# tuner.net
KiCad netlist of a schematic drawn in EAGLE
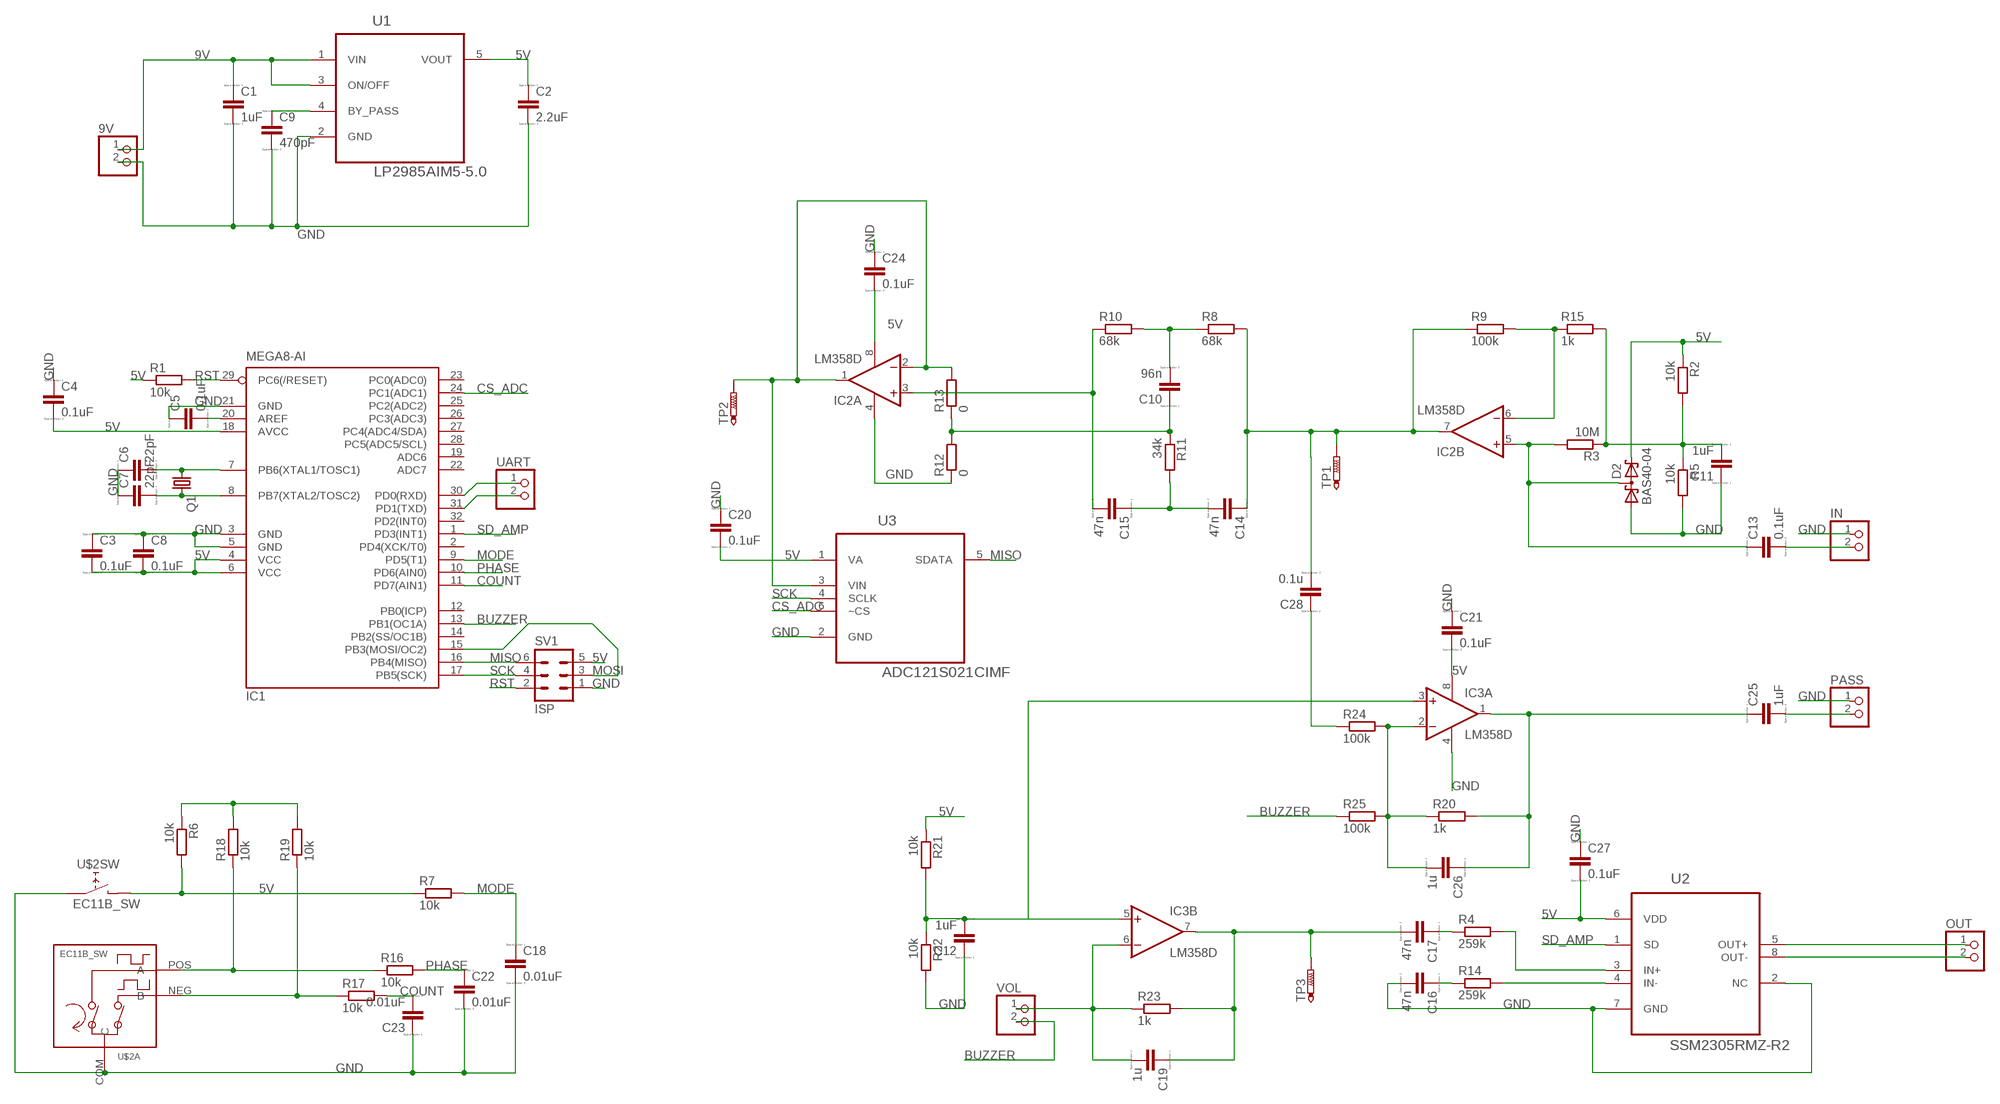
[diagram p0: schematic, sheet 1]

(export (version "E")
  (design (tool "Eeschema 10.0.6"))
  (components
    (comp (ref "9V")
      (value "PINHD-1X2")
      (footprint "eagle-import:1X02")
      (libsource (lib "eagle-import") (part "PINHD-1X2"))
    )
    (comp (ref "C1")
      (value "1uF")
      (footprint "eagle-import:C0805")
      (libsource (lib "eagle-import") (part "C"))
    )
    (comp (ref "C2")
      (value "2.2uF")
      (footprint "eagle-import:C0805")
      (libsource (lib "eagle-import") (part "C"))
    )
    (comp (ref "C3")
      (value "0.1uF")
      (footprint "eagle-import:C0805")
      (libsource (lib "eagle-import") (part "C"))
    )
    (comp (ref "C4")
      (value "0.1uF")
      (footprint "eagle-import:C0805")
      (libsource (lib "eagle-import") (part "C"))
    )
    (comp (ref "C5")
      (value "0.1uF")
      (footprint "eagle-import:C0805")
      (libsource (lib "eagle-import") (part "C"))
    )
    (comp (ref "C6")
      (value "22pF")
      (footprint "eagle-import:C0805")
      (libsource (lib "eagle-import") (part "C"))
    )
    (comp (ref "C7")
      (value "22pF")
      (footprint "eagle-import:C0805")
      (libsource (lib "eagle-import") (part "C"))
    )
    (comp (ref "C8")
      (value "0.1uF")
      (footprint "eagle-import:C0805")
      (libsource (lib "eagle-import") (part "C"))
    )
    (comp (ref "C9")
      (value "470pF")
      (footprint "eagle-import:C0805")
      (libsource (lib "eagle-import") (part "C"))
    )
    (comp (ref "C10")
      (value "96n")
      (footprint "eagle-import:C0805")
      (libsource (lib "eagle-import") (part "C"))
    )
    (comp (ref "C11")
      (value "1uF")
      (footprint "eagle-import:C0805")
      (libsource (lib "eagle-import") (part "C"))
    )
    (comp (ref "C12")
      (value "1uF")
      (footprint "eagle-import:C0805")
      (libsource (lib "eagle-import") (part "C"))
    )
    (comp (ref "C13")
      (value "0.1uF")
      (footprint "eagle-import:C0805")
      (libsource (lib "eagle-import") (part "C"))
    )
    (comp (ref "C14")
      (value "47n")
      (footprint "eagle-import:C0805")
      (libsource (lib "eagle-import") (part "C"))
    )
    (comp (ref "C15")
      (value "47n")
      (footprint "eagle-import:C0805")
      (libsource (lib "eagle-import") (part "C"))
    )
    (comp (ref "C16")
      (value "47n")
      (footprint "eagle-import:C0805")
      (libsource (lib "eagle-import") (part "C"))
    )
    (comp (ref "C17")
      (value "47n")
      (footprint "eagle-import:C0805")
      (libsource (lib "eagle-import") (part "C"))
    )
    (comp (ref "C18")
      (value "0.01uF")
      (footprint "eagle-import:C0805")
      (libsource (lib "eagle-import") (part "C"))
    )
    (comp (ref "C19")
      (value "1u")
      (footprint "eagle-import:C0805")
      (libsource (lib "eagle-import") (part "C"))
    )
    (comp (ref "C20")
      (value "0.1uF")
      (footprint "eagle-import:C0805")
      (libsource (lib "eagle-import") (part "C"))
    )
    (comp (ref "C21")
      (value "0.1uF")
      (footprint "eagle-import:C0805")
      (libsource (lib "eagle-import") (part "C"))
    )
    (comp (ref "C22")
      (value "0.01uF")
      (footprint "eagle-import:C0805")
      (libsource (lib "eagle-import") (part "C"))
    )
    (comp (ref "C23")
      (value "0.01uF")
      (footprint "eagle-import:C0805")
      (libsource (lib "eagle-import") (part "C"))
    )
    (comp (ref "C24")
      (value "0.1uF")
      (footprint "eagle-import:C0805")
      (libsource (lib "eagle-import") (part "C"))
    )
    (comp (ref "C25")
      (value "1uF")
      (footprint "eagle-import:C0805")
      (libsource (lib "eagle-import") (part "C"))
    )
    (comp (ref "C26")
      (value "1u")
      (footprint "eagle-import:C0805")
      (libsource (lib "eagle-import") (part "C"))
    )
    (comp (ref "C27")
      (value "0.1uF")
      (footprint "eagle-import:C0805")
      (libsource (lib "eagle-import") (part "C"))
    )
    (comp (ref "C28")
      (value "0.1u")
      (footprint "eagle-import:C0805")
      (libsource (lib "eagle-import") (part "C"))
    )
    (comp (ref "D2")
      (value "BAS40-04")
      (footprint "eagle-import:SOT23")
      (libsource (lib "eagle-import") (part "BAS40-04"))
    )
    (comp (ref "IC1")
      (value "MEGA8-AI")
      (footprint "eagle-import:TQFP32-08")
      (fields (field (name "MPN") "ATMEGA8-16AU"))
      (libsource (lib "eagle-import") (part "MEGA8-AI"))
    )
    (comp (ref "IC2")
      (value "LM358D")
      (footprint "eagle-import:SO08")
      (libsource (lib "eagle-import") (part "LM358D"))
    )
    (comp (ref "IC3")
      (value "LM358D")
      (footprint "eagle-import:SO08")
      (libsource (lib "eagle-import") (part "LM358D"))
    )
    (comp (ref "IN")
      (value "PINHD-1X2")
      (footprint "eagle-import:1X02")
      (libsource (lib "eagle-import") (part "PINHD-1X2"))
    )
    (comp (ref "OUT")
      (value "PINHD-1X2")
      (footprint "eagle-import:1X02")
      (libsource (lib "eagle-import") (part "PINHD-1X2"))
    )
    (comp (ref "PASS")
      (value "PINHD-1X2")
      (footprint "eagle-import:1X02")
      (libsource (lib "eagle-import") (part "PINHD-1X2"))
    )
    (comp (ref "Q1")
      (value "CRYSTALHC49S")
      (footprint "eagle-import:HC49_S")
      (libsource (lib "eagle-import") (part "CRYSTALHC49S"))
    )
    (comp (ref "R1")
      (value "10k")
      (footprint "eagle-import:M0805")
      (libsource (lib "eagle-import") (part "R-EU_M0805"))
    )
    (comp (ref "R2")
      (value "10k")
      (footprint "eagle-import:M0805")
      (libsource (lib "eagle-import") (part "R-EU_M0805"))
    )
    (comp (ref "R3")
      (value "10M")
      (footprint "eagle-import:M0805")
      (libsource (lib "eagle-import") (part "R-EU_M0805"))
    )
    (comp (ref "R4")
      (value "259k")
      (footprint "eagle-import:M0805")
      (libsource (lib "eagle-import") (part "R-EU_M0805"))
    )
    (comp (ref "R5")
      (value "10k")
      (footprint "eagle-import:M0805")
      (libsource (lib "eagle-import") (part "R-EU_M0805"))
    )
    (comp (ref "R6")
      (value "10k")
      (footprint "eagle-import:M0805")
      (libsource (lib "eagle-import") (part "R-EU_M0805"))
    )
    (comp (ref "R7")
      (value "10k")
      (footprint "eagle-import:M0805")
      (libsource (lib "eagle-import") (part "R-EU_M0805"))
    )
    (comp (ref "R8")
      (value "68k")
      (footprint "eagle-import:M0805")
      (libsource (lib "eagle-import") (part "R-EU_M0805"))
    )
    (comp (ref "R9")
      (value "100k")
      (footprint "eagle-import:M0805")
      (libsource (lib "eagle-import") (part "R-EU_M0805"))
    )
    (comp (ref "R10")
      (value "68k")
      (footprint "eagle-import:M0805")
      (libsource (lib "eagle-import") (part "R-EU_M0805"))
    )
    (comp (ref "R11")
      (value "34k")
      (footprint "eagle-import:M0805")
      (libsource (lib "eagle-import") (part "R-EU_M0805"))
    )
    (comp (ref "R12")
      (value "0")
      (footprint "eagle-import:M0805")
      (libsource (lib "eagle-import") (part "R-EU_M0805"))
    )
    (comp (ref "R13")
      (value "0")
      (footprint "eagle-import:M0805")
      (libsource (lib "eagle-import") (part "R-EU_M0805"))
    )
    (comp (ref "R14")
      (value "259k")
      (footprint "eagle-import:M0805")
      (libsource (lib "eagle-import") (part "R-EU_M0805"))
    )
    (comp (ref "R15")
      (value "1k")
      (footprint "eagle-import:M0805")
      (libsource (lib "eagle-import") (part "R-EU_M0805"))
    )
    (comp (ref "R16")
      (value "10k")
      (footprint "eagle-import:M0805")
      (libsource (lib "eagle-import") (part "R-EU_M0805"))
    )
    (comp (ref "R17")
      (value "10k")
      (footprint "eagle-import:M0805")
      (libsource (lib "eagle-import") (part "R-EU_M0805"))
    )
    (comp (ref "R18")
      (value "10k")
      (footprint "eagle-import:M0805")
      (libsource (lib "eagle-import") (part "R-EU_M0805"))
    )
    (comp (ref "R19")
      (value "10k")
      (footprint "eagle-import:M0805")
      (libsource (lib "eagle-import") (part "R-EU_M0805"))
    )
    (comp (ref "R20")
      (value "1k")
      (footprint "eagle-import:M0805")
      (libsource (lib "eagle-import") (part "R-EU_M0805"))
    )
    (comp (ref "R21")
      (value "10k")
      (footprint "eagle-import:M0805")
      (libsource (lib "eagle-import") (part "R-EU_M0805"))
    )
    (comp (ref "R22")
      (value "10k")
      (footprint "eagle-import:M0805")
      (libsource (lib "eagle-import") (part "R-EU_M0805"))
    )
    (comp (ref "R23")
      (value "1k")
      (footprint "eagle-import:M0805")
      (libsource (lib "eagle-import") (part "R-EU_M0805"))
    )
    (comp (ref "R24")
      (value "100k")
      (footprint "eagle-import:M0805")
      (libsource (lib "eagle-import") (part "R-EU_M0805"))
    )
    (comp (ref "R25")
      (value "100k")
      (footprint "eagle-import:M0805")
      (libsource (lib "eagle-import") (part "R-EU_M0805"))
    )
    (comp (ref "SV1")
      (value "ISP")
      (footprint "eagle-import:MA03-2")
      (libsource (lib "eagle-import") (part "MA03-2"))
    )
    (comp (ref "TP1")
      (value "PTR1B1,27")
      (footprint "eagle-import:B1,27")
      (libsource (lib "eagle-import") (part "PTR1B1,27"))
    )
    (comp (ref "TP2")
      (value "PTR1B1,27")
      (footprint "eagle-import:B1,27")
      (libsource (lib "eagle-import") (part "PTR1B1,27"))
    )
    (comp (ref "TP3")
      (value "PTR1B1,27")
      (footprint "eagle-import:B1,27")
      (libsource (lib "eagle-import") (part "PTR1B1,27"))
    )
    (comp (ref "U$2")
      (value "EC11B_SW")
      (footprint "eagle-import:EC11B")
      (libsource (lib "eagle-import") (part "EC11B_SW"))
    )
    (comp (ref "U1")
      (value "LP2985AIM5-5.0")
      (footprint "eagle-import:SOT95P284X119-5N")
      (fields (field (name "MF") "Texas Instruments") (field (name "MP") "LP2985AIM5-5.0/NOPB"))
      (libsource (lib "eagle-import") (part "LP2985AIM5-5.0"))
    )
    (comp (ref "U2")
      (value "SSM2305RMZ-R2")
      (footprint "eagle-import:SOP65P490X110-8N")
      (fields (field (name "MF") "Analog Devices"))
      (libsource (lib "eagle-import") (part "SSM2305RMZ-R2"))
    )
    (comp (ref "U3")
      (value "ADC121S021CIMF")
      (footprint "eagle-import:SOT95P284X122-6N")
      (fields (field (name "MF") "Texas Instruments") (field (name "MP") "ADC121S021CIMF/NOPB"))
      (libsource (lib "eagle-import") (part "ADC121S021CIMF"))
    )
    (comp (ref "UART")
      (value "PINHD-1X2")
      (footprint "eagle-import:1X02")
      (libsource (lib "eagle-import") (part "PINHD-1X2"))
    )
    (comp (ref "VOL")
      (value "PINHD-1X2")
      (footprint "eagle-import:1X02")
      (libsource (lib "eagle-import") (part "PINHD-1X2"))
    )
  )
  (nets
    (net (code "1") (name "/5V") (class "Default")
      (node (ref "C2") (pin "1") (pinfunction "1_1") (pintype "passive"))
      (node (ref "C20") (pin "2") (pinfunction "2_2") (pintype "passive"))
      (node (ref "C21") (pin "2") (pinfunction "2_2") (pintype "passive"))
      (node (ref "C24") (pin "2") (pinfunction "2_2") (pintype "passive"))
      (node (ref "C27") (pin "2") (pinfunction "2_2") (pintype "passive"))
      (node (ref "C3") (pin "2") (pinfunction "2_2") (pintype "passive"))
      (node (ref "C4") (pin "2") (pinfunction "2_2") (pintype "passive"))
      (node (ref "C8") (pin "2") (pinfunction "2_2") (pintype "passive"))
      (node (ref "D2") (pin "2") (pinfunction "C2_2") (pintype "passive"))
      (node (ref "IC1") (pin "18") (pinfunction "AVCC_18") (pintype "power_in"))
      (node (ref "IC1") (pin "4") (pinfunction "VCC_4") (pintype "power_in"))
      (node (ref "IC1") (pin "6") (pinfunction "VCC_6") (pintype "power_in"))
      (node (ref "IC2") (pin "8") (pinfunction "V+_8") (pintype "power_in"))
      (node (ref "IC3") (pin "8") (pinfunction "V+_8") (pintype "power_in"))
      (node (ref "R1") (pin "1") (pinfunction "1_1") (pintype "passive"))
      (node (ref "R18") (pin "2") (pinfunction "2_2") (pintype "passive"))
      (node (ref "R19") (pin "2") (pinfunction "2_2") (pintype "passive"))
      (node (ref "R2") (pin "1") (pinfunction "1_1") (pintype "passive"))
      (node (ref "R21") (pin "1") (pinfunction "1_1") (pintype "passive"))
      (node (ref "R6") (pin "1") (pinfunction "1_1") (pintype "passive"))
      (node (ref "SV1") (pin "5") (pinfunction "5_5") (pintype "passive"))
      (node (ref "U1") (pin "5") (pinfunction "VOUT_5") (pintype "output"))
      (node (ref "U2") (pin "6") (pinfunction "VDD_6") (pintype "power_in"))
      (node (ref "U3") (pin "1") (pinfunction "VA_1") (pintype "power_in"))
    )
    (net (code "2") (name "/9V") (class "Default")
      (node (ref "9V") (pin "1") (pinfunction "1_1") (pintype "passive"))
      (node (ref "C1") (pin "1") (pinfunction "1_1") (pintype "passive"))
      (node (ref "U1") (pin "1") (pinfunction "VIN_1") (pintype "power_in"))
      (node (ref "U1") (pin "3") (pinfunction "ON/OFF_3") (pintype "input"))
    )
    (net (code "3") (name "/BUZZER") (class "Default")
      (node (ref "IC1") (pin "13") (pinfunction "PB1(OC1A)_13") (pintype "bidirectional"))
      (node (ref "R25") (pin "1") (pinfunction "1_1") (pintype "passive"))
      (node (ref "VOL") (pin "2") (pinfunction "2_2") (pintype "passive"))
    )
    (net (code "4") (name "/COUNT") (class "Default")
      (node (ref "C23") (pin "2") (pinfunction "2_2") (pintype "passive"))
      (node (ref "IC1") (pin "11") (pinfunction "PD7(AIN1)_11") (pintype "bidirectional"))
      (node (ref "R17") (pin "2") (pinfunction "2_2") (pintype "passive"))
    )
    (net (code "5") (name "/CS_ADC") (class "Default")
      (node (ref "IC1") (pin "24") (pinfunction "PC1(ADC1)_24") (pintype "bidirectional"))
      (node (ref "U3") (pin "6") (pinfunction "~{CS}_6") (pintype "input"))
    )
    (net (code "6") (name "/GND") (class "Default")
      (node (ref "9V") (pin "2") (pinfunction "2_2") (pintype "passive"))
      (node (ref "C1") (pin "2") (pinfunction "2_2") (pintype "passive"))
      (node (ref "C11") (pin "1") (pinfunction "1_1") (pintype "passive"))
      (node (ref "C12") (pin "1") (pinfunction "1_1") (pintype "passive"))
      (node (ref "C16") (pin "2") (pinfunction "2_2") (pintype "passive"))
      (node (ref "C18") (pin "2") (pinfunction "2_2") (pintype "passive"))
      (node (ref "C2") (pin "2") (pinfunction "2_2") (pintype "passive"))
      (node (ref "C20") (pin "1") (pinfunction "1_1") (pintype "passive"))
      (node (ref "C21") (pin "1") (pinfunction "1_1") (pintype "passive"))
      (node (ref "C22") (pin "2") (pinfunction "2_2") (pintype "passive"))
      (node (ref "C23") (pin "1") (pinfunction "1_1") (pintype "passive"))
      (node (ref "C24") (pin "1") (pinfunction "1_1") (pintype "passive"))
      (node (ref "C27") (pin "1") (pinfunction "1_1") (pintype "passive"))
      (node (ref "C3") (pin "1") (pinfunction "1_1") (pintype "passive"))
      (node (ref "C4") (pin "1") (pinfunction "1_1") (pintype "passive"))
      (node (ref "C5") (pin "1") (pinfunction "1_1") (pintype "passive"))
      (node (ref "C6") (pin "1") (pinfunction "1_1") (pintype "passive"))
      (node (ref "C7") (pin "1") (pinfunction "1_1") (pintype "passive"))
      (node (ref "C8") (pin "1") (pinfunction "1_1") (pintype "passive"))
      (node (ref "C9") (pin "2") (pinfunction "2_2") (pintype "passive"))
      (node (ref "D2") (pin "1") (pinfunction "A1_1") (pintype "passive"))
      (node (ref "IC1") (pin "21") (pinfunction "GND_21") (pintype "power_in"))
      (node (ref "IC1") (pin "3") (pinfunction "GND_3") (pintype "power_in"))
      (node (ref "IC1") (pin "5") (pinfunction "GND_5") (pintype "power_in"))
      (node (ref "IC2") (pin "4") (pinfunction "V-_4") (pintype "power_in"))
      (node (ref "IC3") (pin "4") (pinfunction "V-_4") (pintype "power_in"))
      (node (ref "IN") (pin "1") (pinfunction "1_1") (pintype "passive"))
      (node (ref "PASS") (pin "1") (pinfunction "1_1") (pintype "passive"))
      (node (ref "R12") (pin "1") (pinfunction "1_1") (pintype "passive"))
      (node (ref "R22") (pin "2") (pinfunction "2_2") (pintype "passive"))
      (node (ref "R5") (pin "2") (pinfunction "2_2") (pintype "passive"))
      (node (ref "SV1") (pin "1") (pinfunction "1_1") (pintype "passive"))
      (node (ref "U$2") (pin "COM") (pinfunction "C_COM") (pintype "bidirectional"))
      (node (ref "U$2") (pin "SW1") (pinfunction "D_SW1") (pintype "passive"))
      (node (ref "U1") (pin "2") (pinfunction "GND_2") (pintype "passive"))
      (node (ref "U2") (pin "2") (pinfunction "NC_2") (pintype "passive"))
      (node (ref "U2") (pin "7") (pinfunction "GND_7") (pintype "passive"))
      (node (ref "U3") (pin "2") (pinfunction "GND_2") (pintype "passive"))
    )
    (net (code "7") (name "/MISO") (class "Default")
      (node (ref "IC1") (pin "16") (pinfunction "PB4(MISO)_16") (pintype "bidirectional"))
      (node (ref "SV1") (pin "6") (pinfunction "6_6") (pintype "passive"))
      (node (ref "U3") (pin "5") (pinfunction "SDATA_5") (pintype "output"))
    )
    (net (code "8") (name "/MODE") (class "Default")
      (node (ref "C18") (pin "1") (pinfunction "1_1") (pintype "passive"))
      (node (ref "IC1") (pin "9") (pinfunction "PD5(T1)_9") (pintype "bidirectional"))
      (node (ref "R7") (pin "2") (pinfunction "2_2") (pintype "passive"))
    )
    (net (code "9") (name "/MOSI") (class "Default")
      (node (ref "IC1") (pin "15") (pinfunction "PB3(MOSI/OC2)_15") (pintype "bidirectional"))
      (node (ref "SV1") (pin "3") (pinfunction "3_3") (pintype "passive"))
    )
    (net (code "10") (name "/PHASE") (class "Default")
      (node (ref "C22") (pin "1") (pinfunction "1_1") (pintype "passive"))
      (node (ref "IC1") (pin "10") (pinfunction "PD6(AIN0)_10") (pintype "bidirectional"))
      (node (ref "R16") (pin "2") (pinfunction "2_2") (pintype "passive"))
    )
    (net (code "11") (name "/RST") (class "Default")
      (node (ref "IC1") (pin "29") (pinfunction "PC6(/RESET)_29") (pintype "bidirectional"))
      (node (ref "R1") (pin "2") (pinfunction "2_2") (pintype "passive"))
      (node (ref "SV1") (pin "2") (pinfunction "2_2") (pintype "passive"))
    )
    (net (code "12") (name "/SCK") (class "Default")
      (node (ref "IC1") (pin "17") (pinfunction "PB5(SCK)_17") (pintype "bidirectional"))
      (node (ref "SV1") (pin "4") (pinfunction "4_4") (pintype "passive"))
      (node (ref "U3") (pin "4") (pinfunction "SCLK_4") (pintype "input"))
    )
    (net (code "13") (name "/SD_AMP") (class "Default")
      (node (ref "IC1") (pin "1") (pinfunction "PD3(INT1)_1") (pintype "bidirectional"))
      (node (ref "U2") (pin "1") (pinfunction "SD_1") (pintype "passive"))
    )
    (net (code "14") (name "Net-(C10-Pad1)") (class "Default")
      (node (ref "C10") (pin "1") (pinfunction "1_1") (pintype "passive"))
      (node (ref "R11") (pin "1") (pinfunction "1_1") (pintype "passive"))
      (node (ref "R12") (pin "2") (pinfunction "2_2") (pintype "passive"))
      (node (ref "R13") (pin "1") (pinfunction "1_1") (pintype "passive"))
    )
    (net (code "15") (name "Net-(C10-Pad2)") (class "Default")
      (node (ref "C10") (pin "2") (pinfunction "2_2") (pintype "passive"))
      (node (ref "R10") (pin "2") (pinfunction "2_2") (pintype "passive"))
      (node (ref "R8") (pin "1") (pinfunction "1_1") (pintype "passive"))
    )
    (net (code "16") (name "Net-(C11-Pad2)") (class "Default")
      (node (ref "C11") (pin "2") (pinfunction "2_2") (pintype "passive"))
      (node (ref "R15") (pin "2") (pinfunction "2_2") (pintype "passive"))
      (node (ref "R2") (pin "2") (pinfunction "2_2") (pintype "passive"))
      (node (ref "R3") (pin "1") (pinfunction "1_1") (pintype "passive"))
      (node (ref "R5") (pin "1") (pinfunction "1_1") (pintype "passive"))
    )
    (net (code "17") (name "Net-(C13-Pad2)") (class "Default")
      (node (ref "C13") (pin "2") (pinfunction "2_2") (pintype "passive"))
      (node (ref "IN") (pin "2") (pinfunction "2_2") (pintype "passive"))
    )
    (net (code "18") (name "Net-(C14-Pad2)") (class "Default")
      (node (ref "C14") (pin "2") (pinfunction "2_2") (pintype "passive"))
      (node (ref "C15") (pin "1") (pinfunction "1_1") (pintype "passive"))
      (node (ref "R11") (pin "2") (pinfunction "2_2") (pintype "passive"))
    )
    (net (code "19") (name "Net-(C16-Pad1)") (class "Default")
      (node (ref "C16") (pin "1") (pinfunction "1_1") (pintype "passive"))
      (node (ref "R14") (pin "1") (pinfunction "1_1") (pintype "passive"))
    )
    (net (code "20") (name "Net-(C17-Pad1)") (class "Default")
      (node (ref "C17") (pin "1") (pinfunction "1_1") (pintype "passive"))
      (node (ref "R4") (pin "1") (pinfunction "1_1") (pintype "passive"))
    )
    (net (code "21") (name "Net-(C25-Pad2)") (class "Default")
      (node (ref "C25") (pin "2") (pinfunction "2_2") (pintype "passive"))
      (node (ref "PASS") (pin "2") (pinfunction "2_2") (pintype "passive"))
    )
    (net (code "22") (name "Net-(C28-Pad1)") (class "Default")
      (node (ref "C28") (pin "1") (pinfunction "1_1") (pintype "passive"))
      (node (ref "R24") (pin "1") (pinfunction "1_1") (pintype "passive"))
    )
    (net (code "23") (name "Net-(D2-C1A2)") (class "Default")
      (node (ref "C13") (pin "1") (pinfunction "1_1") (pintype "passive"))
      (node (ref "D2") (pin "3") (pinfunction "C1A2_3") (pintype "passive"))
      (node (ref "IC2") (pin "5") (pinfunction "+IN_5") (pintype "input"))
      (node (ref "R3") (pin "2") (pinfunction "2_2") (pintype "passive"))
    )
    (net (code "24") (name "Net-(IC1-AREF)") (class "Default")
      (node (ref "C5") (pin "2") (pinfunction "2_2") (pintype "passive"))
      (node (ref "IC1") (pin "20") (pinfunction "AREF_20") (pintype "passive"))
    )
    (net (code "25") (name "Net-(IC1-PB6(XTAL1{slash}TOSC1))") (class "Default")
      (node (ref "C6") (pin "2") (pinfunction "2_2") (pintype "passive"))
      (node (ref "IC1") (pin "7") (pinfunction "PB6(XTAL1/TOSC1)_7") (pintype "bidirectional"))
      (node (ref "Q1") (pin "1") (pinfunction "1_1") (pintype "passive"))
    )
    (net (code "26") (name "Net-(IC1-PB7(XTAL2{slash}TOSC2))") (class "Default")
      (node (ref "C7") (pin "2") (pinfunction "2_2") (pintype "passive"))
      (node (ref "IC1") (pin "8") (pinfunction "PB7(XTAL2/TOSC2)_8") (pintype "bidirectional"))
      (node (ref "Q1") (pin "2") (pinfunction "2_2") (pintype "passive"))
    )
    (net (code "27") (name "Net-(IC1-PD0(RXD))") (class "Default")
      (node (ref "IC1") (pin "30") (pinfunction "PD0(RXD)_30") (pintype "bidirectional"))
      (node (ref "UART") (pin "1") (pinfunction "1_1") (pintype "passive"))
    )
    (net (code "28") (name "Net-(IC1-PD1(TXD))") (class "Default")
      (node (ref "IC1") (pin "31") (pinfunction "PD1(TXD)_31") (pintype "bidirectional"))
      (node (ref "UART") (pin "2") (pinfunction "2_2") (pintype "passive"))
    )
    (net (code "29") (name "Net-(IC2A-+IN)") (class "Default")
      (node (ref "C15") (pin "2") (pinfunction "2_2") (pintype "passive"))
      (node (ref "IC2") (pin "3") (pinfunction "+IN_3") (pintype "input"))
      (node (ref "R10") (pin "1") (pinfunction "1_1") (pintype "passive"))
    )
    (net (code "30") (name "Net-(IC2A--IN)") (class "Default")
      (node (ref "IC2") (pin "1") (pinfunction "OUT_1") (pintype "output"))
      (node (ref "IC2") (pin "2") (pinfunction "-IN_2") (pintype "input"))
      (node (ref "R13") (pin "2") (pinfunction "2_2") (pintype "passive"))
      (node (ref "TP2") (pin "TP") (pinfunction "TP_TP") (pintype "input"))
      (node (ref "U3") (pin "3") (pinfunction "VIN_3") (pintype "input"))
    )
    (net (code "31") (name "Net-(IC2B--IN)") (class "Default")
      (node (ref "IC2") (pin "6") (pinfunction "-IN_6") (pintype "input"))
      (node (ref "R15") (pin "1") (pinfunction "1_1") (pintype "passive"))
      (node (ref "R9") (pin "2") (pinfunction "2_2") (pintype "passive"))
    )
    (net (code "32") (name "Net-(IC2B-OUT)") (class "Default")
      (node (ref "C14") (pin "1") (pinfunction "1_1") (pintype "passive"))
      (node (ref "C28") (pin "2") (pinfunction "2_2") (pintype "passive"))
      (node (ref "IC2") (pin "7") (pinfunction "OUT_7") (pintype "output"))
      (node (ref "R8") (pin "2") (pinfunction "2_2") (pintype "passive"))
      (node (ref "R9") (pin "1") (pinfunction "1_1") (pintype "passive"))
      (node (ref "TP1") (pin "TP") (pinfunction "TP_TP") (pintype "input"))
    )
    (net (code "33") (name "Net-(IC3A-+IN)") (class "Default")
      (node (ref "C12") (pin "2") (pinfunction "2_2") (pintype "passive"))
      (node (ref "IC3") (pin "3") (pinfunction "+IN_3") (pintype "input"))
      (node (ref "IC3") (pin "5") (pinfunction "+IN_5") (pintype "input"))
      (node (ref "R21") (pin "2") (pinfunction "2_2") (pintype "passive"))
      (node (ref "R22") (pin "1") (pinfunction "1_1") (pintype "passive"))
    )
    (net (code "34") (name "Net-(IC3A--IN)") (class "Default")
      (node (ref "C26") (pin "2") (pinfunction "2_2") (pintype "passive"))
      (node (ref "IC3") (pin "2") (pinfunction "-IN_2") (pintype "input"))
      (node (ref "R20") (pin "1") (pinfunction "1_1") (pintype "passive"))
      (node (ref "R24") (pin "2") (pinfunction "2_2") (pintype "passive"))
      (node (ref "R25") (pin "2") (pinfunction "2_2") (pintype "passive"))
    )
    (net (code "35") (name "Net-(IC3A-OUT)") (class "Default")
      (node (ref "C25") (pin "1") (pinfunction "1_1") (pintype "passive"))
      (node (ref "C26") (pin "1") (pinfunction "1_1") (pintype "passive"))
      (node (ref "IC3") (pin "1") (pinfunction "OUT_1") (pintype "output"))
      (node (ref "R20") (pin "2") (pinfunction "2_2") (pintype "passive"))
    )
    (net (code "36") (name "Net-(IC3B--IN)") (class "Default")
      (node (ref "C19") (pin "2") (pinfunction "2_2") (pintype "passive"))
      (node (ref "IC3") (pin "6") (pinfunction "-IN_6") (pintype "input"))
      (node (ref "R23") (pin "1") (pinfunction "1_1") (pintype "passive"))
      (node (ref "VOL") (pin "1") (pinfunction "1_1") (pintype "passive"))
    )
    (net (code "37") (name "Net-(IC3B-OUT)") (class "Default")
      (node (ref "C17") (pin "2") (pinfunction "2_2") (pintype "passive"))
      (node (ref "C19") (pin "1") (pinfunction "1_1") (pintype "passive"))
      (node (ref "IC3") (pin "7") (pinfunction "OUT_7") (pintype "output"))
      (node (ref "R23") (pin "2") (pinfunction "2_2") (pintype "passive"))
      (node (ref "TP3") (pin "TP") (pinfunction "TP_TP") (pintype "input"))
    )
    (net (code "38") (name "Net-(U$2A-A)") (class "Default")
      (node (ref "R16") (pin "1") (pinfunction "1_1") (pintype "passive"))
      (node (ref "R18") (pin "1") (pinfunction "1_1") (pintype "passive"))
      (node (ref "U$2") (pin "POS") (pinfunction "A_POS") (pintype "bidirectional"))
    )
    (net (code "39") (name "Net-(U$2A-B)") (class "Default")
      (node (ref "R17") (pin "1") (pinfunction "1_1") (pintype "passive"))
      (node (ref "R19") (pin "1") (pinfunction "1_1") (pintype "passive"))
      (node (ref "U$2") (pin "NEG") (pinfunction "B_NEG") (pintype "bidirectional"))
    )
    (net (code "40") (name "Net-(U$2B-E)") (class "Default")
      (node (ref "R6") (pin "2") (pinfunction "2_2") (pintype "passive"))
      (node (ref "R7") (pin "1") (pinfunction "1_1") (pintype "passive"))
      (node (ref "U$2") (pin "SW2") (pinfunction "E_SW2") (pintype "passive"))
    )
    (net (code "41") (name "Net-(U1-BY_PASS)") (class "Default")
      (node (ref "C9") (pin "1") (pinfunction "1_1") (pintype "passive"))
      (node (ref "U1") (pin "4") (pinfunction "BY_PASS_4") (pintype "passive"))
    )
    (net (code "42") (name "Net-(U2-IN+)") (class "Default")
      (node (ref "R4") (pin "2") (pinfunction "2_2") (pintype "passive"))
      (node (ref "U2") (pin "3") (pinfunction "IN+_3") (pintype "passive"))
    )
    (net (code "43") (name "Net-(U2-IN-)") (class "Default")
      (node (ref "R14") (pin "2") (pinfunction "2_2") (pintype "passive"))
      (node (ref "U2") (pin "4") (pinfunction "IN-_4") (pintype "passive"))
    )
    (net (code "44") (name "Net-(U2-OUT+)") (class "Default")
      (node (ref "OUT") (pin "1") (pinfunction "1_1") (pintype "passive"))
      (node (ref "U2") (pin "5") (pinfunction "OUT+_5") (pintype "passive"))
    )
    (net (code "45") (name "Net-(U2-OUT-)") (class "Default")
      (node (ref "OUT") (pin "2") (pinfunction "2_2") (pintype "passive"))
      (node (ref "U2") (pin "8") (pinfunction "OUT-_8") (pintype "passive"))
    )
    (net (code "46") (name "unconnected-(IC1-ADC6-Pad19)") (class "Default")
      (node (ref "IC1") (pin "19") (pinfunction "ADC6_19") (pintype "bidirectional"))
    )
    (net (code "47") (name "unconnected-(IC1-ADC7-Pad22)") (class "Default")
      (node (ref "IC1") (pin "22") (pinfunction "ADC7_22") (pintype "bidirectional"))
    )
    (net (code "48") (name "unconnected-(IC1-PB0(ICP)-Pad12)") (class "Default")
      (node (ref "IC1") (pin "12") (pinfunction "PB0(ICP)_12") (pintype "bidirectional"))
    )
    (net (code "49") (name "unconnected-(IC1-PB2(SS{slash}OC1B)-Pad14)") (class "Default")
      (node (ref "IC1") (pin "14") (pinfunction "PB2(SS/OC1B)_14") (pintype "bidirectional"))
    )
    (net (code "50") (name "unconnected-(IC1-PC0(ADC0)-Pad23)") (class "Default")
      (node (ref "IC1") (pin "23") (pinfunction "PC0(ADC0)_23") (pintype "bidirectional"))
    )
    (net (code "51") (name "unconnected-(IC1-PC2(ADC2)-Pad25)") (class "Default")
      (node (ref "IC1") (pin "25") (pinfunction "PC2(ADC2)_25") (pintype "bidirectional"))
    )
    (net (code "52") (name "unconnected-(IC1-PC3(ADC3)-Pad26)") (class "Default")
      (node (ref "IC1") (pin "26") (pinfunction "PC3(ADC3)_26") (pintype "bidirectional"))
    )
    (net (code "53") (name "unconnected-(IC1-PC4(ADC4{slash}SDA)-Pad27)") (class "Default")
      (node (ref "IC1") (pin "27") (pinfunction "PC4(ADC4/SDA)_27") (pintype "bidirectional"))
    )
    (net (code "54") (name "unconnected-(IC1-PC5(ADC5{slash}SCL)-Pad28)") (class "Default")
      (node (ref "IC1") (pin "28") (pinfunction "PC5(ADC5/SCL)_28") (pintype "bidirectional"))
    )
    (net (code "55") (name "unconnected-(IC1-PD2(INT0)-Pad32)") (class "Default")
      (node (ref "IC1") (pin "32") (pinfunction "PD2(INT0)_32") (pintype "bidirectional"))
    )
    (net (code "56") (name "unconnected-(IC1-PD4(XCK{slash}T0)-Pad2)") (class "Default")
      (node (ref "IC1") (pin "2") (pinfunction "PD4(XCK/T0)_2") (pintype "bidirectional"))
    )
  )
)
